# esp8266-bme280-deepsleep.net
KiCad netlist of a schematic drawn in EAGLE
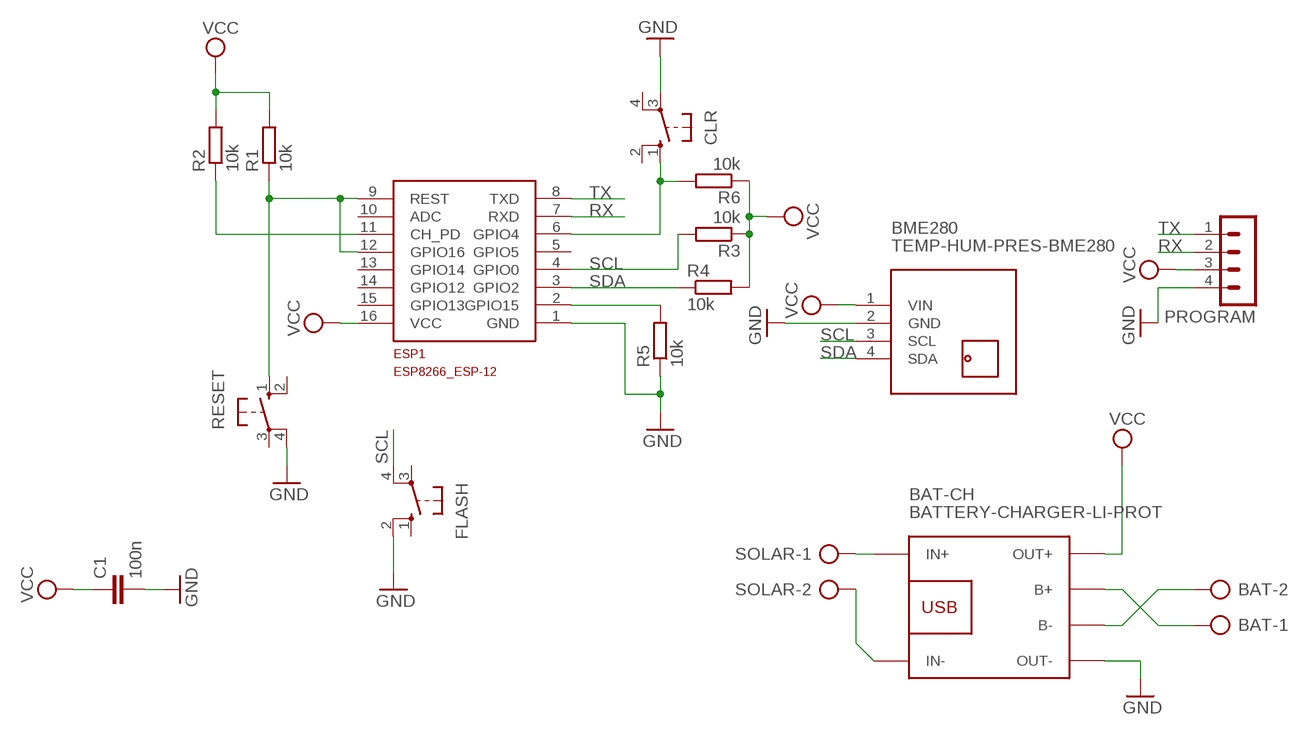
[diagram p0: schematic, sheet 1]

(export (version "E")
  (design (tool "Eeschema 10.0.6"))
  (components
    (comp (ref "BAT")
      (value "PWR_CONN_KK")
      (footprint "eagle-import:PWR_CONN_KK_5MM")
      (libsource (lib "eagle-import") (part "PWR_CONN_KK"))
    )
    (comp (ref "BAT-CH")
      (value "BATTERY-CHARGER-LI-PROT")
      (footprint "eagle-import:BATTERY-CHARGER-LI-PROT")
      (libsource (lib "eagle-import") (part "BATTERY-CHARGER-LI-PROT"))
    )
    (comp (ref "BME280")
      (value "TEMP-HUM-PRES-BME280")
      (footprint "eagle-import:TEMP-HUM-PRES-BME280")
      (libsource (lib "eagle-import") (part "TEMP-HUM-PRES-BME280"))
    )
    (comp (ref "C1")
      (value "100n")
      (footprint "eagle-import:C2.5-3")
      (libsource (lib "eagle-import") (part "C2,5-3"))
    )
    (comp (ref "CLR")
      (value "10-XX")
      (footprint "eagle-import:B3F-10XX")
      (fields (field (name "MPN") "B3F-1000"))
      (libsource (lib "eagle-import") (part "10-XX"))
    )
    (comp (ref "ESP1")
      (value "ESP8266_ESP-12")
      (footprint "eagle-import:ESP8266-ESP12")
      (libsource (lib "eagle-import") (part "ESP8266_ESP-12"))
    )
    (comp (ref "FLASH")
      (value "10-XX")
      (footprint "eagle-import:B3F-10XX")
      (fields (field (name "MPN") "B3F-1000"))
      (libsource (lib "eagle-import") (part "10-XX"))
    )
    (comp (ref "PROGRAM")
      (value "MA04-1")
      (footprint "eagle-import:MA04-1")
      (libsource (lib "eagle-import") (part "MA04-1"))
    )
    (comp (ref "R1")
      (value "10k")
      (footprint "eagle-import:0204_7")
      (libsource (lib "eagle-import") (part "R-EU_0204/7"))
    )
    (comp (ref "R2")
      (value "10k")
      (footprint "eagle-import:0204_7")
      (libsource (lib "eagle-import") (part "R-EU_0204/7"))
    )
    (comp (ref "R3")
      (value "10k")
      (footprint "eagle-import:0204_7")
      (libsource (lib "eagle-import") (part "R-EU_0204/7"))
    )
    (comp (ref "R4")
      (value "10k")
      (footprint "eagle-import:0204_7")
      (libsource (lib "eagle-import") (part "R-EU_0204/7"))
    )
    (comp (ref "R5")
      (value "10k")
      (footprint "eagle-import:0204_7")
      (libsource (lib "eagle-import") (part "R-EU_0204/7"))
    )
    (comp (ref "R6")
      (value "10k")
      (footprint "eagle-import:0204_7")
      (libsource (lib "eagle-import") (part "R-EU_0204/7"))
    )
    (comp (ref "RESET")
      (value "10-XX")
      (footprint "eagle-import:B3F-10XX")
      (fields (field (name "MPN") "B3F-1000"))
      (libsource (lib "eagle-import") (part "10-XX"))
    )
    (comp (ref "SOLAR")
      (value "PWR_CONN_KK")
      (footprint "eagle-import:PWR_CONN_KK_5MM")
      (libsource (lib "eagle-import") (part "PWR_CONN_KK"))
    )
  )
  (nets
    (net (code "1") (name "/RX") (class "Default")
      (node (ref "ESP1") (pin "7") (pinfunction "RXD_7") (pintype "bidirectional"))
      (node (ref "PROGRAM") (pin "2") (pinfunction "2_2") (pintype "passive"))
    )
    (net (code "2") (name "/SCL") (class "Default")
      (node (ref "BME280") (pin "3") (pinfunction "SCL_3") (pintype "bidirectional"))
      (node (ref "ESP1") (pin "4") (pinfunction "GPIO0_4") (pintype "bidirectional"))
      (node (ref "FLASH") (pin "4") (pinfunction "P1_4") (pintype "passive"))
      (node (ref "R3") (pin "2") (pinfunction "2_2") (pintype "passive"))
    )
    (net (code "3") (name "/SDA") (class "Default")
      (node (ref "BME280") (pin "4") (pinfunction "SDA_4") (pintype "bidirectional"))
      (node (ref "ESP1") (pin "3") (pinfunction "GPIO2_3") (pintype "bidirectional"))
      (node (ref "R4") (pin "1") (pinfunction "1_1") (pintype "passive"))
    )
    (net (code "4") (name "/TX") (class "Default")
      (node (ref "ESP1") (pin "8") (pinfunction "TXD_8") (pintype "bidirectional"))
      (node (ref "PROGRAM") (pin "1") (pinfunction "1_1") (pintype "passive"))
    )
    (net (code "5") (name "GND") (class "Default")
      (node (ref "BAT-CH") (pin "OUT-") (pinfunction "OUT-_OUT-") (pintype "bidirectional"))
      (node (ref "BME280") (pin "2") (pinfunction "GND_2") (pintype "power_in"))
      (node (ref "C1") (pin "2") (pinfunction "2_2") (pintype "passive"))
      (node (ref "CLR") (pin "3") (pinfunction "P_3") (pintype "passive"))
      (node (ref "ESP1") (pin "1") (pinfunction "GND_1") (pintype "bidirectional"))
      (node (ref "FLASH") (pin "2") (pinfunction "S1_2") (pintype "passive"))
      (node (ref "PROGRAM") (pin "4") (pinfunction "4_4") (pintype "passive"))
      (node (ref "R5") (pin "1") (pinfunction "1_1") (pintype "passive"))
      (node (ref "RESET") (pin "4") (pinfunction "P1_4") (pintype "passive"))
    )
    (net (code "6") (name "Net-(BATA-KL)") (class "Default")
      (node (ref "BAT") (pin "1") (pinfunction "KL_1") (pintype "passive"))
      (node (ref "BAT-CH") (pin "B+") (pinfunction "B+_B+") (pintype "bidirectional"))
    )
    (net (code "7") (name "Net-(BATB-KL)") (class "Default")
      (node (ref "BAT") (pin "2") (pinfunction "KL_2") (pintype "passive"))
      (node (ref "BAT-CH") (pin "B-") (pinfunction "B-_B-") (pintype "bidirectional"))
    )
    (net (code "8") (name "Net-(CLR-S)") (class "Default")
      (node (ref "CLR") (pin "1") (pinfunction "S_1") (pintype "passive"))
      (node (ref "ESP1") (pin "6") (pinfunction "GPIO4_6") (pintype "bidirectional"))
      (node (ref "R6") (pin "2") (pinfunction "2_2") (pintype "passive"))
    )
    (net (code "9") (name "Net-(ESP1-CH_PD)") (class "Default")
      (node (ref "ESP1") (pin "11") (pinfunction "CH_PD_11") (pintype "bidirectional"))
      (node (ref "R2") (pin "1") (pinfunction "1_1") (pintype "passive"))
    )
    (net (code "10") (name "Net-(ESP1-GPIO15)") (class "Default")
      (node (ref "ESP1") (pin "2") (pinfunction "GPIO15_2") (pintype "bidirectional"))
      (node (ref "R5") (pin "2") (pinfunction "2_2") (pintype "passive"))
    )
    (net (code "11") (name "Net-(ESP1-GPIO16)") (class "Default")
      (node (ref "ESP1") (pin "12") (pinfunction "GPIO16_12") (pintype "bidirectional"))
      (node (ref "ESP1") (pin "9") (pinfunction "REST_9") (pintype "bidirectional"))
      (node (ref "R1") (pin "1") (pinfunction "1_1") (pintype "passive"))
      (node (ref "RESET") (pin "1") (pinfunction "S_1") (pintype "passive"))
    )
    (net (code "12") (name "Net-(SOLARA-KL)") (class "Default")
      (node (ref "BAT-CH") (pin "IN+") (pinfunction "IN+_IN+") (pintype "bidirectional"))
      (node (ref "SOLAR") (pin "1") (pinfunction "KL_1") (pintype "passive"))
    )
    (net (code "13") (name "Net-(SOLARB-KL)") (class "Default")
      (node (ref "BAT-CH") (pin "IN-") (pinfunction "IN-_IN-") (pintype "bidirectional"))
      (node (ref "SOLAR") (pin "2") (pinfunction "KL_2") (pintype "passive"))
    )
    (net (code "14") (name "VCC") (class "Default")
      (node (ref "BAT-CH") (pin "OUT+") (pinfunction "OUT+_OUT+") (pintype "bidirectional"))
      (node (ref "BME280") (pin "1") (pinfunction "VIN_1") (pintype "power_in"))
      (node (ref "C1") (pin "1") (pinfunction "1_1") (pintype "passive"))
      (node (ref "ESP1") (pin "16") (pinfunction "VCC_16") (pintype "bidirectional"))
      (node (ref "PROGRAM") (pin "3") (pinfunction "3_3") (pintype "passive"))
      (node (ref "R1") (pin "2") (pinfunction "2_2") (pintype "passive"))
      (node (ref "R2") (pin "2") (pinfunction "2_2") (pintype "passive"))
      (node (ref "R3") (pin "1") (pinfunction "1_1") (pintype "passive"))
      (node (ref "R4") (pin "2") (pinfunction "2_2") (pintype "passive"))
      (node (ref "R6") (pin "1") (pinfunction "1_1") (pintype "passive"))
    )
    (net (code "15") (name "unconnected-(CLR-P1-Pad4)") (class "Default")
      (node (ref "CLR") (pin "4") (pinfunction "P1_4") (pintype "passive"))
    )
    (net (code "16") (name "unconnected-(CLR-S1-Pad2)") (class "Default")
      (node (ref "CLR") (pin "2") (pinfunction "S1_2") (pintype "passive"))
    )
    (net (code "17") (name "unconnected-(ESP1-ADC-Pad10)") (class "Default")
      (node (ref "ESP1") (pin "10") (pinfunction "ADC_10") (pintype "bidirectional"))
    )
    (net (code "18") (name "unconnected-(ESP1-GPIO5-Pad5)") (class "Default")
      (node (ref "ESP1") (pin "5") (pinfunction "GPIO5_5") (pintype "bidirectional"))
    )
    (net (code "19") (name "unconnected-(ESP1-GPIO12-Pad14)") (class "Default")
      (node (ref "ESP1") (pin "14") (pinfunction "GPIO12_14") (pintype "bidirectional"))
    )
    (net (code "20") (name "unconnected-(ESP1-GPIO13-Pad15)") (class "Default")
      (node (ref "ESP1") (pin "15") (pinfunction "GPIO13_15") (pintype "bidirectional"))
    )
    (net (code "21") (name "unconnected-(ESP1-GPIO14-Pad13)") (class "Default")
      (node (ref "ESP1") (pin "13") (pinfunction "GPIO14_13") (pintype "bidirectional"))
    )
    (net (code "22") (name "unconnected-(FLASH-P-Pad3)") (class "Default")
      (node (ref "FLASH") (pin "3") (pinfunction "P_3") (pintype "passive"))
    )
    (net (code "23") (name "unconnected-(FLASH-S-Pad1)") (class "Default")
      (node (ref "FLASH") (pin "1") (pinfunction "S_1") (pintype "passive"))
    )
    (net (code "24") (name "unconnected-(RESET-P-Pad3)") (class "Default")
      (node (ref "RESET") (pin "3") (pinfunction "P_3") (pintype "passive"))
    )
    (net (code "25") (name "unconnected-(RESET-S1-Pad2)") (class "Default")
      (node (ref "RESET") (pin "2") (pinfunction "S1_2") (pintype "passive"))
    )
  )
)
